# Bandit_the_Racoon.net
KiCad netlist of a schematic drawn in EAGLE
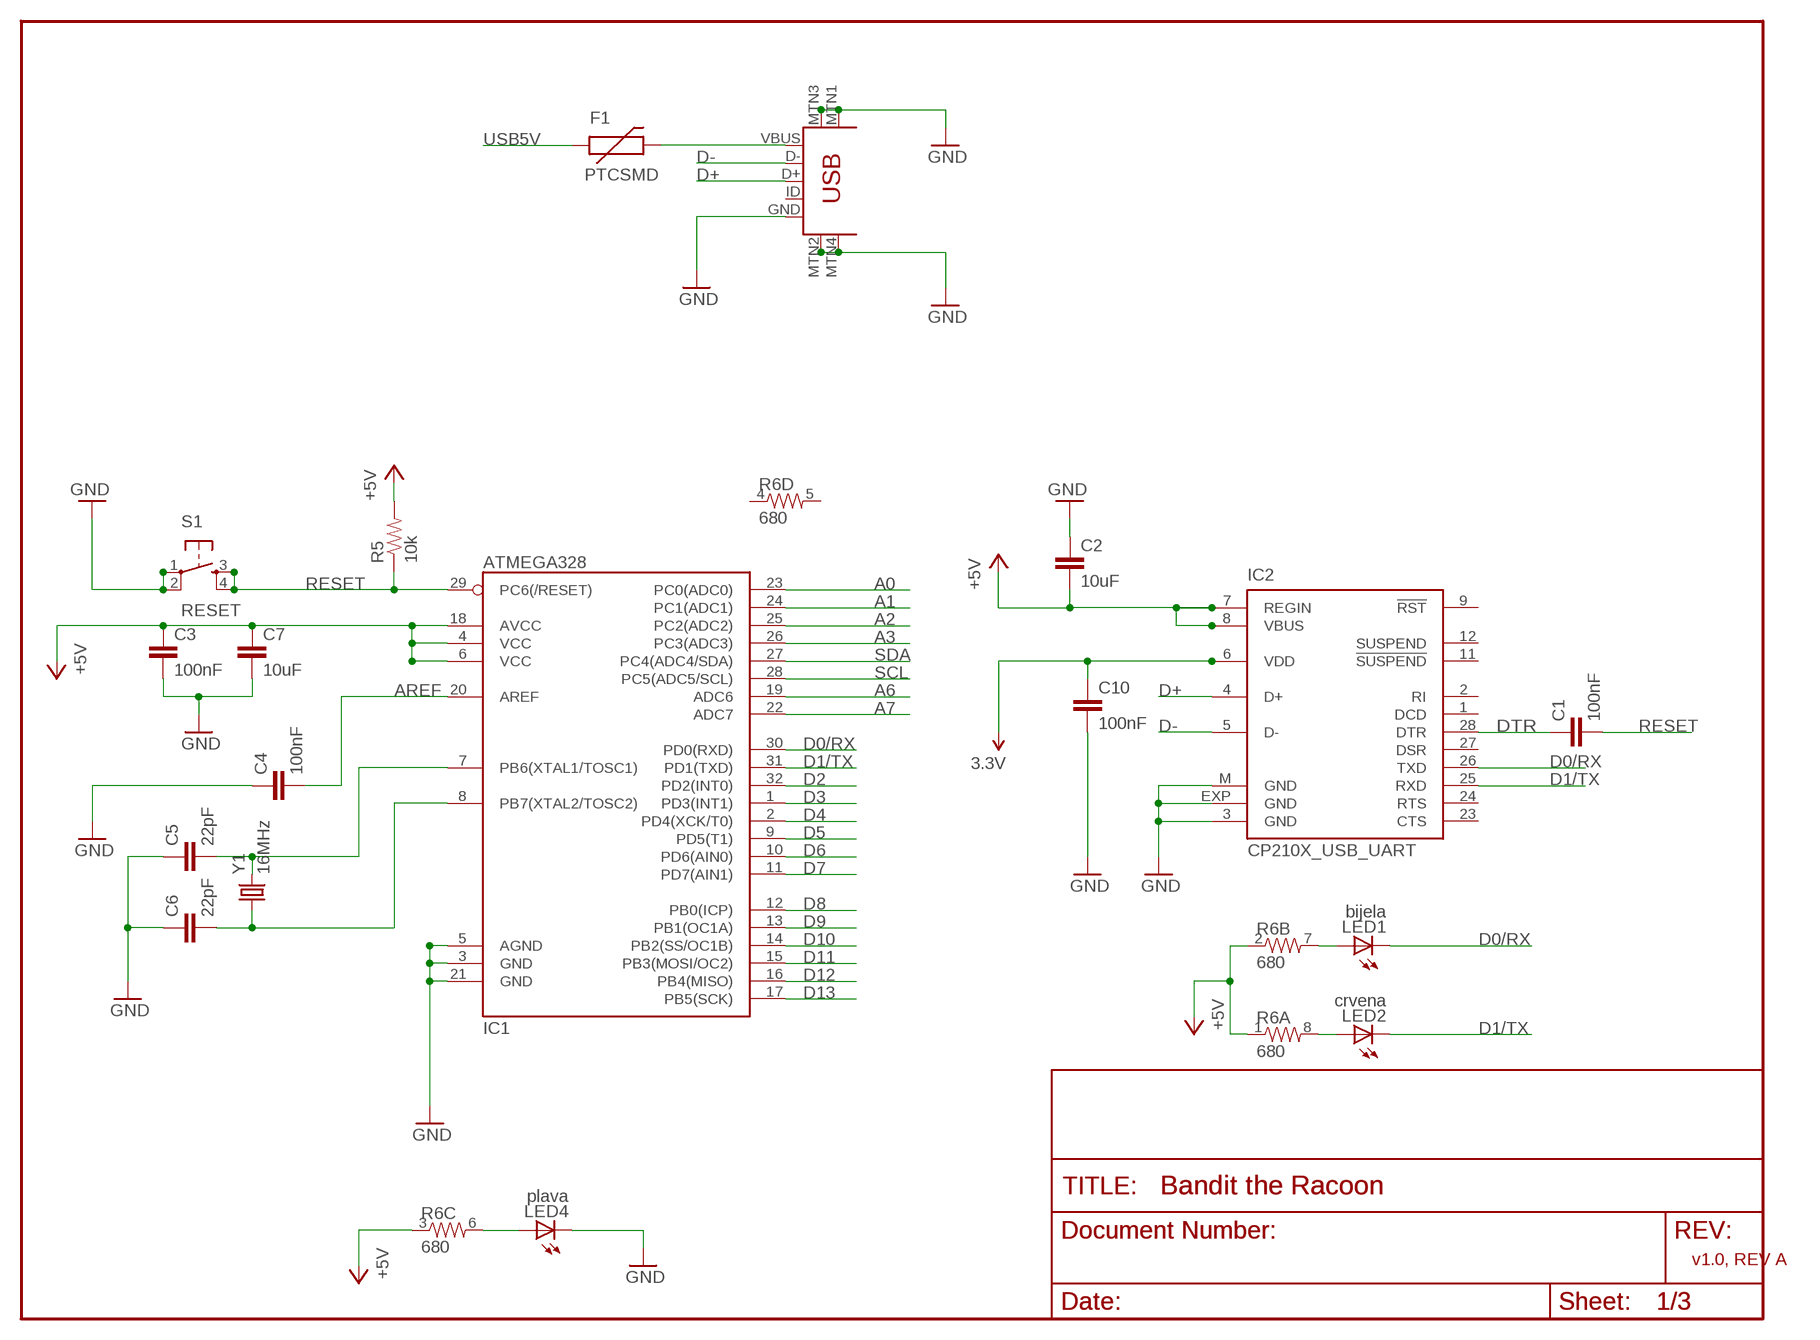
[diagram p0: schematic, sheet 1]
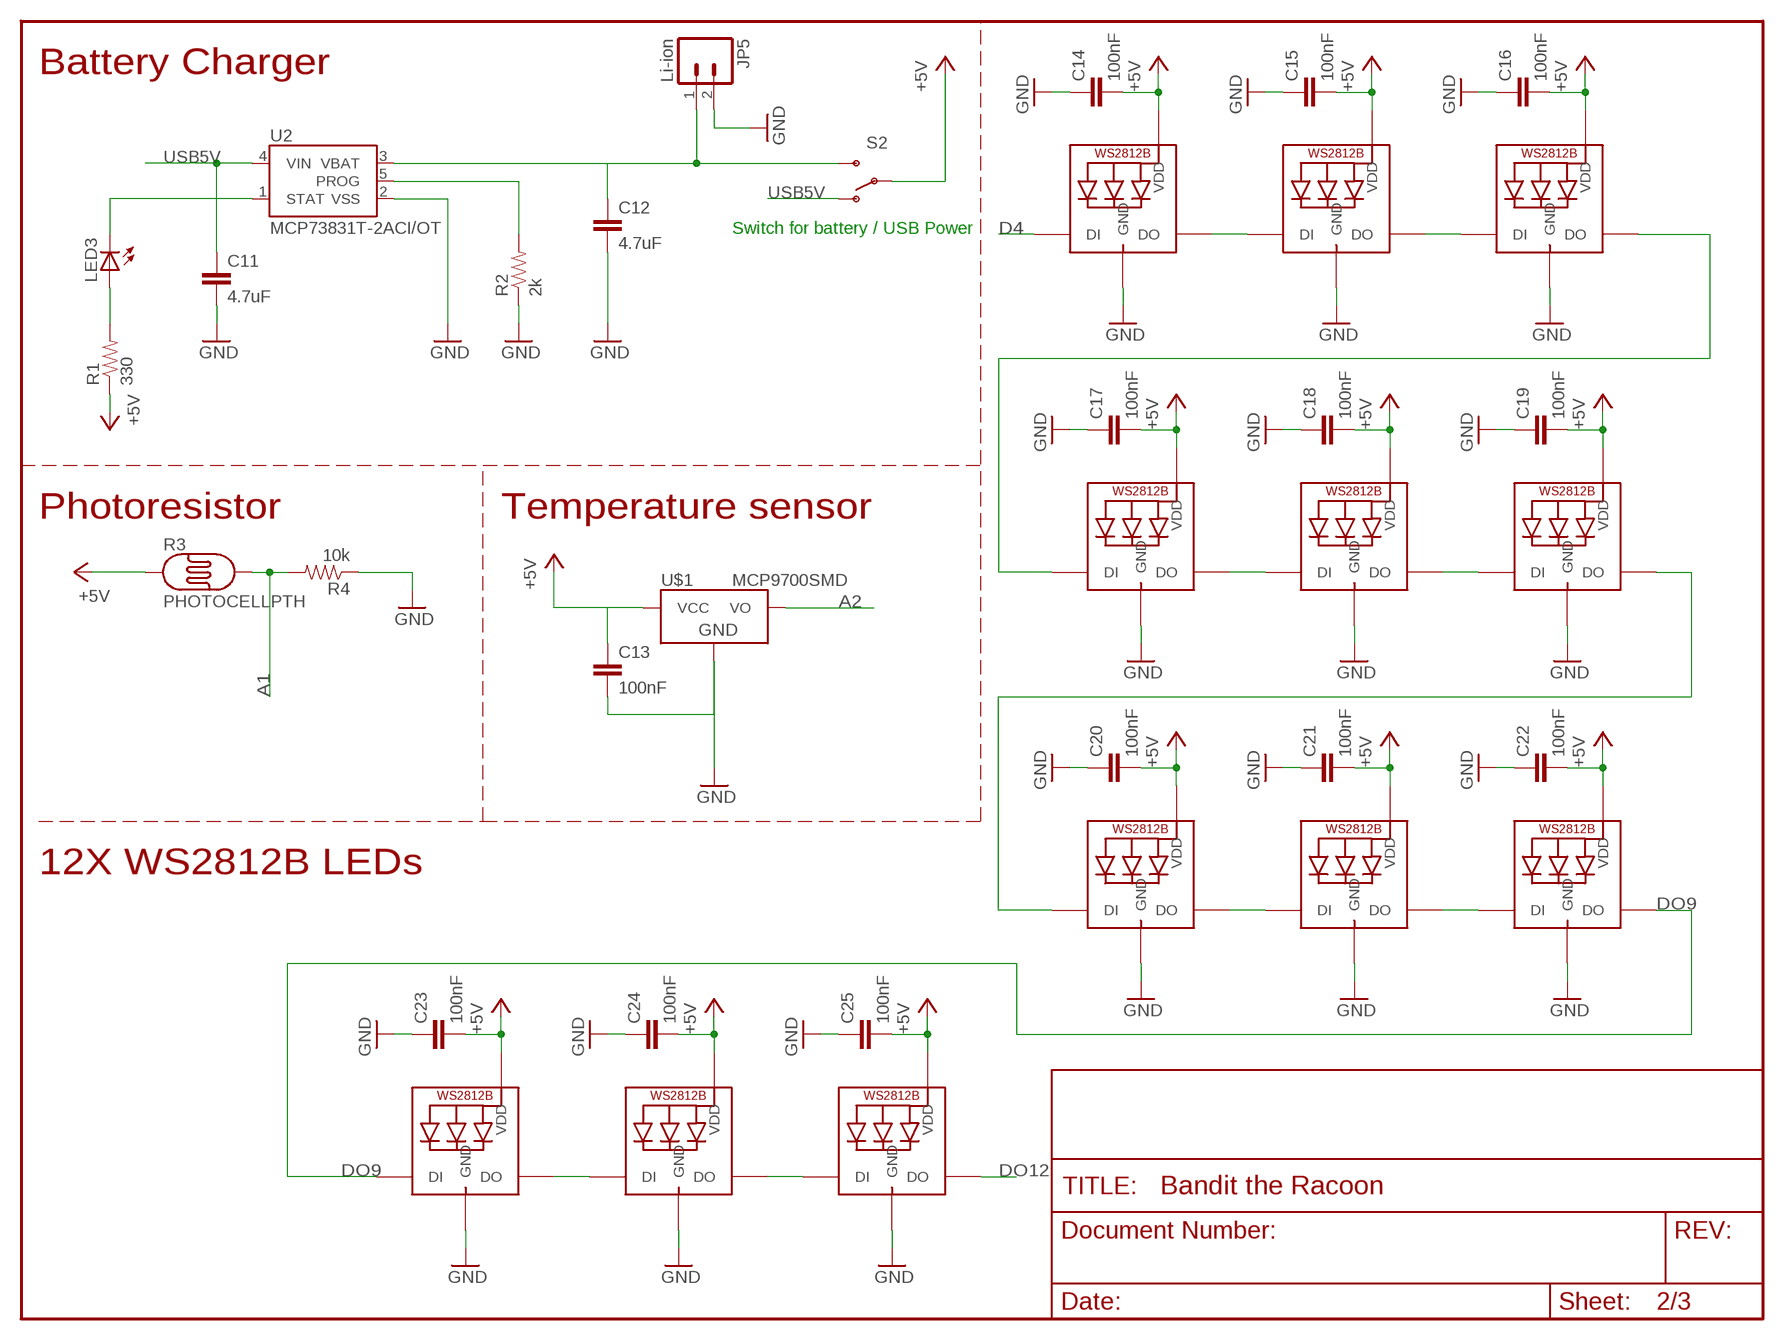
[diagram p1: schematic, sheet 2]
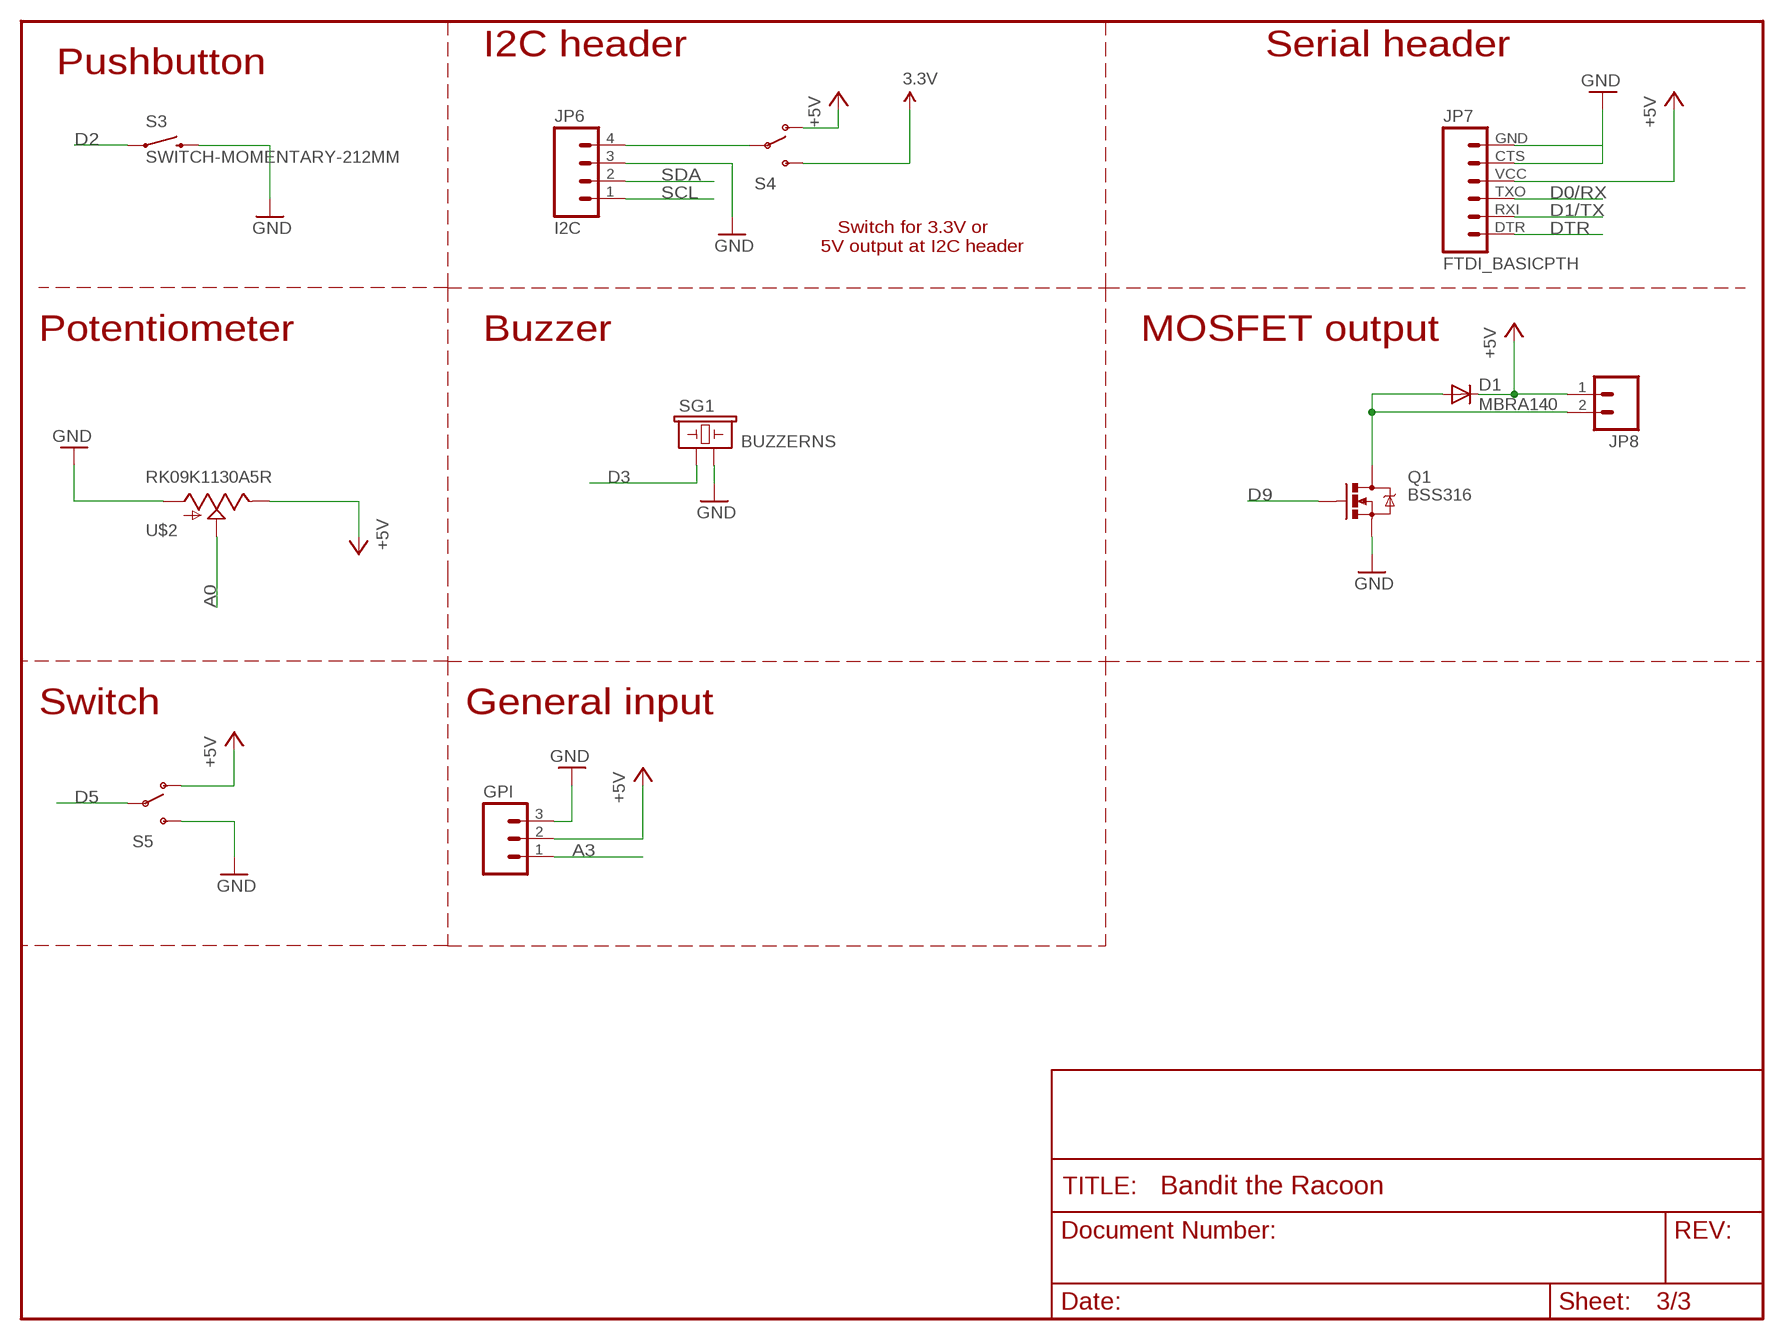
[diagram p2: schematic, sheet 3]

(export (version "E")
  (design (tool "Eeschema 10.0.6"))
  (components
    (comp (ref "C1")
      (value "100nF")
      (footprint "eagle-import:0603-CAP")
      (libsource (lib "eagle-import") (part "CAP0603-CAP"))
    )
    (comp (ref "C2")
      (value "10uF")
      (footprint "eagle-import:C3216")
      (libsource (lib "eagle-import") (part "C-EUC3216"))
    )
    (comp (ref "C3")
      (value "100nF")
      (footprint "eagle-import:0603-CAP")
      (libsource (lib "eagle-import") (part "CAP0603-CAP"))
    )
    (comp (ref "C4")
      (value "100nF")
      (footprint "eagle-import:0603-CAP")
      (libsource (lib "eagle-import") (part "CAP0603-CAP"))
    )
    (comp (ref "C5")
      (value "22pF")
      (footprint "eagle-import:0603-CAP")
      (libsource (lib "eagle-import") (part "CAP0603-CAP"))
    )
    (comp (ref "C6")
      (value "22pF")
      (footprint "eagle-import:0603-CAP")
      (libsource (lib "eagle-import") (part "CAP0603-CAP"))
    )
    (comp (ref "C7")
      (value "10uF")
      (footprint "eagle-import:C3216")
      (libsource (lib "eagle-import") (part "C-EUC3216"))
    )
    (comp (ref "C10")
      (value "100nF")
      (footprint "eagle-import:0603-CAP")
      (libsource (lib "eagle-import") (part "CAP0603-CAP"))
    )
    (comp (ref "F1")
      (value "PTCSMD")
      (footprint "eagle-import:PTC-1206")
      (libsource (lib "eagle-import") (part "PTCSMD"))
    )
    (comp (ref "IC1")
      (value "ATMEGA328")
      (footprint "eagle-import:TQFP32-08")
      (libsource (lib "eagle-import") (part "ATMEGA168"))
    )
    (comp (ref "IC2")
      (value "CP210X_USB_UART")
      (footprint "eagle-import:MLP28")
      (libsource (lib "eagle-import") (part "CP210X_USB_UART"))
    )
    (comp (ref "LED1")
      (value "bijela")
      (footprint "eagle-import:CHIP-LED0805")
      (libsource (lib "eagle-import") (part "LEDCHIP-LED0805"))
    )
    (comp (ref "LED2")
      (value "crvena")
      (footprint "eagle-import:CHIP-LED0805")
      (libsource (lib "eagle-import") (part "LEDCHIP-LED0805"))
    )
    (comp (ref "LED4")
      (value "plava")
      (footprint "eagle-import:CHIP-LED0805")
      (libsource (lib "eagle-import") (part "LEDCHIP-LED0805"))
    )
    (comp (ref "R5")
      (value "10k")
      (footprint "eagle-import:0603-RES")
      (libsource (lib "eagle-import") (part "RESISTOR0603-RES"))
    )
    (comp (ref "R6")
      (value "680")
      (footprint "eagle-import:0603-ARV")
      (libsource (lib "eagle-import") (part "RESISTOR-ARRAY0603-ARV"))
    )
    (comp (ref "S1")
      (value "RESET")
      (footprint "eagle-import:TACTILE_SWITCH_SMD")
      (libsource (lib "eagle-import") (part "TAC_SWITCHSMD"))
    )
    (comp (ref "U1")
      (value "USB-MINIB")
      (footprint "eagle-import:USB-MINIB")
      (libsource (lib "eagle-import") (part "USB-MINIB-5PIN"))
    )
    (comp (ref "Y1")
      (value "16MHz")
      (footprint "eagle-import:CRYSTAL-SMD-5X3")
      (libsource (lib "eagle-import") (part "CRYSTAL5X3"))
    )
    (comp (ref "C11")
      (value "4.7uF")
      (footprint "eagle-import:0805")
      (libsource (lib "eagle-import") (part "CAP0805"))
    )
    (comp (ref "C12")
      (value "4.7uF")
      (footprint "eagle-import:0805")
      (libsource (lib "eagle-import") (part "CAP0805"))
    )
    (comp (ref "C13")
      (value "100nF")
      (footprint "eagle-import:0603-CAP")
      (libsource (lib "eagle-import") (part "CAP0603-CAP"))
    )
    (comp (ref "C14")
      (value "100nF")
      (footprint "eagle-import:0603-CAP")
      (libsource (lib "eagle-import") (part "CAP0603-CAP"))
    )
    (comp (ref "C15")
      (value "100nF")
      (footprint "eagle-import:0603-CAP")
      (libsource (lib "eagle-import") (part "CAP0603-CAP"))
    )
    (comp (ref "C16")
      (value "100nF")
      (footprint "eagle-import:0603-CAP")
      (libsource (lib "eagle-import") (part "CAP0603-CAP"))
    )
    (comp (ref "C17")
      (value "100nF")
      (footprint "eagle-import:0603-CAP")
      (libsource (lib "eagle-import") (part "CAP0603-CAP"))
    )
    (comp (ref "C18")
      (value "100nF")
      (footprint "eagle-import:0603-CAP")
      (libsource (lib "eagle-import") (part "CAP0603-CAP"))
    )
    (comp (ref "C19")
      (value "100nF")
      (footprint "eagle-import:0603-CAP")
      (libsource (lib "eagle-import") (part "CAP0603-CAP"))
    )
    (comp (ref "C20")
      (value "100nF")
      (footprint "eagle-import:0603-CAP")
      (libsource (lib "eagle-import") (part "CAP0603-CAP"))
    )
    (comp (ref "C21")
      (value "100nF")
      (footprint "eagle-import:0603-CAP")
      (libsource (lib "eagle-import") (part "CAP0603-CAP"))
    )
    (comp (ref "C22")
      (value "100nF")
      (footprint "eagle-import:0603-CAP")
      (libsource (lib "eagle-import") (part "CAP0603-CAP"))
    )
    (comp (ref "C23")
      (value "100nF")
      (footprint "eagle-import:0603-CAP")
      (libsource (lib "eagle-import") (part "CAP0603-CAP"))
    )
    (comp (ref "C24")
      (value "100nF")
      (footprint "eagle-import:0603-CAP")
      (libsource (lib "eagle-import") (part "CAP0603-CAP"))
    )
    (comp (ref "C25")
      (value "100nF")
      (footprint "eagle-import:0603-CAP")
      (libsource (lib "eagle-import") (part "CAP0603-CAP"))
    )
    (comp (ref "JP5")
      (value "Li-ion")
      (footprint "eagle-import:JST-2-PTH")
      (libsource (lib "eagle-import") (part "M02JST-PTH-2"))
    )
    (comp (ref "LED3")
      (value "LEDCHIPLED_0805")
      (footprint "eagle-import:CHIPLED_0805")
      (libsource (lib "eagle-import") (part "LEDCHIPLED_0805"))
    )
    (comp (ref "LED5")
      (value "WS2812B5050")
      (footprint "eagle-import:WS2812B")
      (libsource (lib "eagle-import") (part "WS2812B5050"))
    )
    (comp (ref "LED6")
      (value "WS2812B5050")
      (footprint "eagle-import:WS2812B")
      (libsource (lib "eagle-import") (part "WS2812B5050"))
    )
    (comp (ref "LED7")
      (value "WS2812B5050")
      (footprint "eagle-import:WS2812B")
      (libsource (lib "eagle-import") (part "WS2812B5050"))
    )
    (comp (ref "LED8")
      (value "WS2812B5050")
      (footprint "eagle-import:WS2812B")
      (libsource (lib "eagle-import") (part "WS2812B5050"))
    )
    (comp (ref "LED9")
      (value "WS2812B5050")
      (footprint "eagle-import:WS2812B")
      (libsource (lib "eagle-import") (part "WS2812B5050"))
    )
    (comp (ref "LED10")
      (value "WS2812B5050")
      (footprint "eagle-import:WS2812B")
      (libsource (lib "eagle-import") (part "WS2812B5050"))
    )
    (comp (ref "LED11")
      (value "WS2812B5050")
      (footprint "eagle-import:WS2812B")
      (libsource (lib "eagle-import") (part "WS2812B5050"))
    )
    (comp (ref "LED12")
      (value "WS2812B5050")
      (footprint "eagle-import:WS2812B")
      (libsource (lib "eagle-import") (part "WS2812B5050"))
    )
    (comp (ref "LED13")
      (value "WS2812B5050")
      (footprint "eagle-import:WS2812B")
      (libsource (lib "eagle-import") (part "WS2812B5050"))
    )
    (comp (ref "LED14")
      (value "WS2812B5050")
      (footprint "eagle-import:WS2812B")
      (libsource (lib "eagle-import") (part "WS2812B5050"))
    )
    (comp (ref "LED15")
      (value "WS2812B5050")
      (footprint "eagle-import:WS2812B")
      (libsource (lib "eagle-import") (part "WS2812B5050"))
    )
    (comp (ref "LED16")
      (value "WS2812B5050")
      (footprint "eagle-import:WS2812B")
      (libsource (lib "eagle-import") (part "WS2812B5050"))
    )
    (comp (ref "R1")
      (value "330")
      (footprint "eagle-import:0603-RES")
      (libsource (lib "eagle-import") (part "RESISTOR0603-RES"))
    )
    (comp (ref "R2")
      (value "2k")
      (footprint "eagle-import:0603-RES")
      (libsource (lib "eagle-import") (part "RESISTOR0603-RES"))
    )
    (comp (ref "R3")
      (value "PHOTOCELLPTH")
      (footprint "eagle-import:PHOTOCELL")
      (libsource (lib "eagle-import") (part "PHOTOCELLPTH"))
    )
    (comp (ref "R4")
      (value "10k")
      (footprint "eagle-import:0603-RES")
      (libsource (lib "eagle-import") (part "RESISTOR0603-RES"))
    )
    (comp (ref "S2")
      (value "SWITCH-SPST-SMD-A")
      (footprint "eagle-import:SWITCH-SPST-SMD-A")
      (libsource (lib "eagle-import") (part "SWITCH-SPST-SMD-A"))
    )
    (comp (ref "U$1")
      (value "MCP9700SMD")
      (footprint "eagle-import:SOT23-3")
      (libsource (lib "eagle-import") (part "MCP9700SMD"))
    )
    (comp (ref "U2")
      (value "MCP73831T-2ACI/OT")
      (footprint "eagle-import:SOT23-5")
      (libsource (lib "eagle-import") (part "MCP73831"))
    )
    (comp (ref "D1")
      (value "MBRA140")
      (footprint "eagle-import:SMA-DIODE")
      (libsource (lib "eagle-import") (part "DIODESMA"))
    )
    (comp (ref "GPI")
      (value "M03LONGPADS")
      (footprint "eagle-import:1X03_LONGPADS")
      (libsource (lib "eagle-import") (part "M03LONGPADS"))
    )
    (comp (ref "JP6")
      (value "I2C")
      (footprint "eagle-import:1X04_LONGPADS")
      (libsource (lib "eagle-import") (part "M04LONGPADS"))
    )
    (comp (ref "JP7")
      (value "FTDI_BASICPTH")
      (footprint "eagle-import:FTDI_BASIC")
      (libsource (lib "eagle-import") (part "FTDI_BASICPTH"))
    )
    (comp (ref "JP8")
      (value "M02PTH")
      (footprint "eagle-import:1X02")
      (libsource (lib "eagle-import") (part "M02PTH"))
    )
    (comp (ref "Q1")
      (value "BSS316")
      (footprint "eagle-import:SOT23-3")
      (libsource (lib "eagle-import") (part "MOSFET-NCHANNELSMD"))
    )
    (comp (ref "S3")
      (value "SWITCH-MOMENTARY-212MM")
      (footprint "eagle-import:TACTILE-PTH-12MM")
      (libsource (lib "eagle-import") (part "SWITCH-MOMENTARY-212MM"))
    )
    (comp (ref "S4")
      (value "SWITCH-SPST-SMD-A")
      (footprint "eagle-import:SWITCH-SPST-SMD-A")
      (libsource (lib "eagle-import") (part "SWITCH-SPST-SMD-A"))
    )
    (comp (ref "S5")
      (value "SWITCH-SPSTKIT")
      (footprint "eagle-import:SWITCH-SPDT_KIT")
      (libsource (lib "eagle-import") (part "SWITCH-SPSTKIT"))
    )
    (comp (ref "SG1")
      (value "BUZZERNS")
      (footprint "eagle-import:BUZZER-12MM-NS")
      (libsource (lib "eagle-import") (part "BUZZERNS"))
    )
    (comp (ref "U$2")
      (value "RK09K1130A5R")
      (footprint "eagle-import:ALPS_POT")
      (libsource (lib "eagle-import") (part "POT"))
    )
  )
  (nets
    (net (code "1") (name "+5V") (class "Default")
      (node (ref "C13") (pin "1") (pinfunction "1_1") (pintype "passive"))
      (node (ref "C14") (pin "2") (pinfunction "2_2") (pintype "passive"))
      (node (ref "C15") (pin "2") (pinfunction "2_2") (pintype "passive"))
      (node (ref "C16") (pin "2") (pinfunction "2_2") (pintype "passive"))
      (node (ref "C17") (pin "2") (pinfunction "2_2") (pintype "passive"))
      (node (ref "C18") (pin "2") (pinfunction "2_2") (pintype "passive"))
      (node (ref "C19") (pin "2") (pinfunction "2_2") (pintype "passive"))
      (node (ref "C2") (pin "2") (pinfunction "2_2") (pintype "passive"))
      (node (ref "C20") (pin "2") (pinfunction "2_2") (pintype "passive"))
      (node (ref "C21") (pin "2") (pinfunction "2_2") (pintype "passive"))
      (node (ref "C22") (pin "2") (pinfunction "2_2") (pintype "passive"))
      (node (ref "C23") (pin "2") (pinfunction "2_2") (pintype "passive"))
      (node (ref "C24") (pin "2") (pinfunction "2_2") (pintype "passive"))
      (node (ref "C25") (pin "2") (pinfunction "2_2") (pintype "passive"))
      (node (ref "C3") (pin "1") (pinfunction "1_1") (pintype "passive"))
      (node (ref "C7") (pin "1") (pinfunction "1_1") (pintype "passive"))
      (node (ref "D1") (pin "C") (pinfunction "C_C") (pintype "passive"))
      (node (ref "GPI") (pin "2") (pinfunction "2_2") (pintype "passive"))
      (node (ref "IC1") (pin "18") (pinfunction "AVCC_18") (pintype "bidirectional"))
      (node (ref "IC1") (pin "4") (pinfunction "VCC_4") (pintype "bidirectional"))
      (node (ref "IC1") (pin "6") (pinfunction "VCC_6") (pintype "bidirectional"))
      (node (ref "IC2") (pin "7") (pinfunction "REGIN_7") (pintype "passive"))
      (node (ref "IC2") (pin "8") (pinfunction "VBUS_8") (pintype "input"))
      (node (ref "JP7") (pin "VCC") (pinfunction "4_VCC") (pintype "passive"))
      (node (ref "JP8") (pin "1") (pinfunction "1_1") (pintype "passive"))
      (node (ref "LED10") (pin "1-VDD") (pinfunction "VDD_1-VDD") (pintype "power_in"))
      (node (ref "LED11") (pin "1-VDD") (pinfunction "VDD_1-VDD") (pintype "power_in"))
      (node (ref "LED12") (pin "1-VDD") (pinfunction "VDD_1-VDD") (pintype "power_in"))
      (node (ref "LED13") (pin "1-VDD") (pinfunction "VDD_1-VDD") (pintype "power_in"))
      (node (ref "LED14") (pin "1-VDD") (pinfunction "VDD_1-VDD") (pintype "power_in"))
      (node (ref "LED15") (pin "1-VDD") (pinfunction "VDD_1-VDD") (pintype "power_in"))
      (node (ref "LED16") (pin "1-VDD") (pinfunction "VDD_1-VDD") (pintype "power_in"))
      (node (ref "LED5") (pin "1-VDD") (pinfunction "VDD_1-VDD") (pintype "power_in"))
      (node (ref "LED6") (pin "1-VDD") (pinfunction "VDD_1-VDD") (pintype "power_in"))
      (node (ref "LED7") (pin "1-VDD") (pinfunction "VDD_1-VDD") (pintype "power_in"))
      (node (ref "LED8") (pin "1-VDD") (pinfunction "VDD_1-VDD") (pintype "power_in"))
      (node (ref "LED9") (pin "1-VDD") (pinfunction "VDD_1-VDD") (pintype "power_in"))
      (node (ref "R1") (pin "1") (pinfunction "1_1") (pintype "passive"))
      (node (ref "R3") (pin "1") (pinfunction "P$1_1") (pintype "bidirectional"))
      (node (ref "R5") (pin "2") (pinfunction "2_2") (pintype "passive"))
      (node (ref "R6") (pin "1") (pinfunction "1_1") (pintype "passive"))
      (node (ref "R6") (pin "2") (pinfunction "1_2") (pintype "passive"))
      (node (ref "R6") (pin "3") (pinfunction "1_3") (pintype "passive"))
      (node (ref "S2") (pin "2") (pinfunction "P_2") (pintype "passive"))
      (node (ref "S4") (pin "1") (pinfunction "O_1") (pintype "passive"))
      (node (ref "S5") (pin "1") (pinfunction "O_1") (pintype "passive"))
      (node (ref "U$1") (pin "1") (pinfunction "VCC_1") (pintype "bidirectional"))
      (node (ref "U$2") (pin "P$1") (pinfunction "E_P$1") (pintype "passive"))
    )
    (net (code "2") (name "3.3V") (class "Default")
      (node (ref "C10") (pin "1") (pinfunction "1_1") (pintype "passive"))
      (node (ref "IC2") (pin "6") (pinfunction "VDD_6") (pintype "power_in"))
      (node (ref "S4") (pin "3") (pinfunction "S_3") (pintype "passive"))
    )
    (net (code "3") (name "A0") (class "Default")
      (node (ref "IC1") (pin "23") (pinfunction "PC0(ADC0)_23") (pintype "bidirectional"))
      (node (ref "U$2") (pin "P$2") (pinfunction "S_P$2") (pintype "passive"))
    )
    (net (code "4") (name "A1") (class "Default")
      (node (ref "IC1") (pin "24") (pinfunction "PC1(ADC1)_24") (pintype "bidirectional"))
      (node (ref "R3") (pin "2") (pinfunction "P$2_2") (pintype "bidirectional"))
      (node (ref "R4") (pin "2") (pinfunction "2_2") (pintype "passive"))
    )
    (net (code "5") (name "A2") (class "Default")
      (node (ref "IC1") (pin "25") (pinfunction "PC2(ADC2)_25") (pintype "bidirectional"))
      (node (ref "U$1") (pin "2") (pinfunction "VO_2") (pintype "bidirectional"))
    )
    (net (code "6") (name "A3") (class "Default")
      (node (ref "GPI") (pin "1") (pinfunction "1_1") (pintype "passive"))
      (node (ref "IC1") (pin "26") (pinfunction "PC3(ADC3)_26") (pintype "bidirectional"))
    )
    (net (code "7") (name "A6") (class "Default")
      (node (ref "IC1") (pin "19") (pinfunction "ADC6_19") (pintype "bidirectional"))
    )
    (net (code "8") (name "A7") (class "Default")
      (node (ref "IC1") (pin "22") (pinfunction "ADC7_22") (pintype "bidirectional"))
    )
    (net (code "9") (name "AREF") (class "Default")
      (node (ref "C4") (pin "2") (pinfunction "2_2") (pintype "passive"))
      (node (ref "IC1") (pin "20") (pinfunction "AREF_20") (pintype "bidirectional"))
    )
    (net (code "10") (name "D+") (class "Default")
      (node (ref "IC2") (pin "4") (pinfunction "D+_4") (pintype "bidirectional"))
      (node (ref "U1") (pin "D+") (pinfunction "D+_D+") (pintype "bidirectional"))
    )
    (net (code "11") (name "D-") (class "Default")
      (node (ref "IC2") (pin "5") (pinfunction "D-_5") (pintype "bidirectional"))
      (node (ref "U1") (pin "D-") (pinfunction "D-_D-") (pintype "bidirectional"))
    )
    (net (code "12") (name "D0{slash}RX") (class "Default")
      (node (ref "IC1") (pin "30") (pinfunction "PD0(RXD)_30") (pintype "bidirectional"))
      (node (ref "IC2") (pin "26") (pinfunction "TXD_26") (pintype "output"))
      (node (ref "JP7") (pin "TXO") (pinfunction "3_TXO") (pintype "passive"))
      (node (ref "LED1") (pin "C") (pinfunction "C_C") (pintype "passive"))
    )
    (net (code "13") (name "D1{slash}TX") (class "Default")
      (node (ref "IC1") (pin "31") (pinfunction "PD1(TXD)_31") (pintype "bidirectional"))
      (node (ref "IC2") (pin "25") (pinfunction "RXD_25") (pintype "input"))
      (node (ref "JP7") (pin "RXI") (pinfunction "2_RXI") (pintype "passive"))
      (node (ref "LED2") (pin "C") (pinfunction "C_C") (pintype "passive"))
    )
    (net (code "14") (name "D2") (class "Default")
      (node (ref "IC1") (pin "32") (pinfunction "PD2(INT0)_32") (pintype "bidirectional"))
      (node (ref "S3") (pin "1") (pinfunction "1_1") (pintype "passive"))
    )
    (net (code "15") (name "D3") (class "Default")
      (node (ref "IC1") (pin "1") (pinfunction "PD3(INT1)_1") (pintype "bidirectional"))
      (node (ref "SG1") (pin "+") (pinfunction "1_+") (pintype "passive"))
    )
    (net (code "16") (name "D4") (class "Default")
      (node (ref "IC1") (pin "2") (pinfunction "PD4(XCK/T0)_2") (pintype "bidirectional"))
      (node (ref "LED5") (pin "4-DIN") (pinfunction "DI_4-DIN") (pintype "input"))
    )
    (net (code "17") (name "D5") (class "Default")
      (node (ref "IC1") (pin "9") (pinfunction "PD5(T1)_9") (pintype "bidirectional"))
      (node (ref "S5") (pin "2") (pinfunction "P_2") (pintype "passive"))
    )
    (net (code "18") (name "D6") (class "Default")
      (node (ref "IC1") (pin "10") (pinfunction "PD6(AIN0)_10") (pintype "bidirectional"))
    )
    (net (code "19") (name "D7") (class "Default")
      (node (ref "IC1") (pin "11") (pinfunction "PD7(AIN1)_11") (pintype "bidirectional"))
    )
    (net (code "20") (name "D8") (class "Default")
      (node (ref "IC1") (pin "12") (pinfunction "PB0(ICP)_12") (pintype "bidirectional"))
    )
    (net (code "21") (name "D9") (class "Default")
      (node (ref "IC1") (pin "13") (pinfunction "PB1(OC1A)_13") (pintype "bidirectional"))
      (node (ref "Q1") (pin "1") (pinfunction "G_1") (pintype "passive"))
    )
    (net (code "22") (name "D10") (class "Default")
      (node (ref "IC1") (pin "14") (pinfunction "PB2(SS/OC1B)_14") (pintype "bidirectional"))
    )
    (net (code "23") (name "D11") (class "Default")
      (node (ref "IC1") (pin "15") (pinfunction "PB3(MOSI/OC2)_15") (pintype "bidirectional"))
    )
    (net (code "24") (name "D12") (class "Default")
      (node (ref "IC1") (pin "16") (pinfunction "PB4(MISO)_16") (pintype "bidirectional"))
    )
    (net (code "25") (name "D13") (class "Default")
      (node (ref "IC1") (pin "17") (pinfunction "PB5(SCK)_17") (pintype "bidirectional"))
    )
    (net (code "26") (name "DO9") (class "Default")
      (node (ref "LED13") (pin "2-DOUT") (pinfunction "DO_2-DOUT") (pintype "output"))
      (node (ref "LED14") (pin "4-DIN") (pinfunction "DI_4-DIN") (pintype "input"))
    )
    (net (code "27") (name "DO12") (class "Default")
      (node (ref "LED16") (pin "2-DOUT") (pinfunction "DO_2-DOUT") (pintype "output"))
    )
    (net (code "28") (name "DTR") (class "Default")
      (node (ref "C1") (pin "1") (pinfunction "1_1") (pintype "passive"))
      (node (ref "IC2") (pin "28") (pinfunction "DTR_28") (pintype "output"))
      (node (ref "JP7") (pin "DTR") (pinfunction "1_DTR") (pintype "passive"))
    )
    (net (code "29") (name "GND") (class "Default")
      (node (ref "C10") (pin "2") (pinfunction "2_2") (pintype "passive"))
      (node (ref "C11") (pin "2") (pinfunction "2_2") (pintype "passive"))
      (node (ref "C12") (pin "2") (pinfunction "2_2") (pintype "passive"))
      (node (ref "C13") (pin "2") (pinfunction "2_2") (pintype "passive"))
      (node (ref "C14") (pin "1") (pinfunction "1_1") (pintype "passive"))
      (node (ref "C15") (pin "1") (pinfunction "1_1") (pintype "passive"))
      (node (ref "C16") (pin "1") (pinfunction "1_1") (pintype "passive"))
      (node (ref "C17") (pin "1") (pinfunction "1_1") (pintype "passive"))
      (node (ref "C18") (pin "1") (pinfunction "1_1") (pintype "passive"))
      (node (ref "C19") (pin "1") (pinfunction "1_1") (pintype "passive"))
      (node (ref "C2") (pin "1") (pinfunction "1_1") (pintype "passive"))
      (node (ref "C20") (pin "1") (pinfunction "1_1") (pintype "passive"))
      (node (ref "C21") (pin "1") (pinfunction "1_1") (pintype "passive"))
      (node (ref "C22") (pin "1") (pinfunction "1_1") (pintype "passive"))
      (node (ref "C23") (pin "1") (pinfunction "1_1") (pintype "passive"))
      (node (ref "C24") (pin "1") (pinfunction "1_1") (pintype "passive"))
      (node (ref "C25") (pin "1") (pinfunction "1_1") (pintype "passive"))
      (node (ref "C3") (pin "2") (pinfunction "2_2") (pintype "passive"))
      (node (ref "C4") (pin "1") (pinfunction "1_1") (pintype "passive"))
      (node (ref "C5") (pin "1") (pinfunction "1_1") (pintype "passive"))
      (node (ref "C6") (pin "1") (pinfunction "1_1") (pintype "passive"))
      (node (ref "C7") (pin "2") (pinfunction "2_2") (pintype "passive"))
      (node (ref "GPI") (pin "3") (pinfunction "3_3") (pintype "passive"))
      (node (ref "IC1") (pin "21") (pinfunction "GND_21") (pintype "bidirectional"))
      (node (ref "IC1") (pin "3") (pinfunction "GND_3") (pintype "bidirectional"))
      (node (ref "IC1") (pin "5") (pinfunction "AGND_5") (pintype "bidirectional"))
      (node (ref "IC2") (pin "3") (pinfunction "GND_3") (pintype "power_in"))
      (node (ref "IC2") (pin "EXP") (pinfunction "GND_EXP") (pintype "power_in"))
      (node (ref "IC2") (pin "M") (pinfunction "GND_M") (pintype "power_in"))
      (node (ref "JP5") (pin "2") (pinfunction "2_2") (pintype "passive"))
      (node (ref "JP6") (pin "3") (pinfunction "3_3") (pintype "passive"))
      (node (ref "JP7") (pin "CTS") (pinfunction "5_CTS") (pintype "passive"))
      (node (ref "JP7") (pin "GND") (pinfunction "6_GND") (pintype "passive"))
      (node (ref "LED10") (pin "3-GND") (pinfunction "GND_3-GND") (pintype "power_in"))
      (node (ref "LED11") (pin "3-GND") (pinfunction "GND_3-GND") (pintype "power_in"))
      (node (ref "LED12") (pin "3-GND") (pinfunction "GND_3-GND") (pintype "power_in"))
      (node (ref "LED13") (pin "3-GND") (pinfunction "GND_3-GND") (pintype "power_in"))
      (node (ref "LED14") (pin "3-GND") (pinfunction "GND_3-GND") (pintype "power_in"))
      (node (ref "LED15") (pin "3-GND") (pinfunction "GND_3-GND") (pintype "power_in"))
      (node (ref "LED16") (pin "3-GND") (pinfunction "GND_3-GND") (pintype "power_in"))
      (node (ref "LED4") (pin "C") (pinfunction "C_C") (pintype "passive"))
      (node (ref "LED5") (pin "3-GND") (pinfunction "GND_3-GND") (pintype "power_in"))
      (node (ref "LED6") (pin "3-GND") (pinfunction "GND_3-GND") (pintype "power_in"))
      (node (ref "LED7") (pin "3-GND") (pinfunction "GND_3-GND") (pintype "power_in"))
      (node (ref "LED8") (pin "3-GND") (pinfunction "GND_3-GND") (pintype "power_in"))
      (node (ref "LED9") (pin "3-GND") (pinfunction "GND_3-GND") (pintype "power_in"))
      (node (ref "Q1") (pin "2") (pinfunction "S_2") (pintype "passive"))
      (node (ref "R2") (pin "1") (pinfunction "1_1") (pintype "passive"))
      (node (ref "R4") (pin "1") (pinfunction "1_1") (pintype "passive"))
      (node (ref "S1") (pin "1") (pinfunction "1_1") (pintype "passive"))
      (node (ref "S1") (pin "2") (pinfunction "2_2") (pintype "passive"))
      (node (ref "S3") (pin "3") (pinfunction "2_3") (pintype "passive"))
      (node (ref "S5") (pin "3") (pinfunction "S_3") (pintype "passive"))
      (node (ref "SG1") (pin "-") (pinfunction "2_-") (pintype "passive"))
      (node (ref "U$1") (pin "3") (pinfunction "GND_3") (pintype "bidirectional"))
      (node (ref "U$2") (pin "P$3") (pinfunction "A_P$3") (pintype "passive"))
      (node (ref "U1") (pin "GND") (pinfunction "GND_GND") (pintype "bidirectional"))
      (node (ref "U1") (pin "MTN1") (pinfunction "MTN2_MTN1") (pintype "bidirectional"))
      (node (ref "U1") (pin "MTN2") (pinfunction "MTN3_MTN2") (pintype "bidirectional"))
      (node (ref "U1") (pin "MTN3") (pinfunction "MTN1_MTN3") (pintype "bidirectional"))
      (node (ref "U1") (pin "MTN4") (pinfunction "MTN4_MTN4") (pintype "bidirectional"))
      (node (ref "U2") (pin "2") (pinfunction "VSS_2") (pintype "power_in"))
    )
    (net (code "30") (name "Net-(F1-Pad2)") (class "Default")
      (node (ref "F1") (pin "2") (pinfunction "2_2") (pintype "bidirectional"))
      (node (ref "U1") (pin "VBUS") (pinfunction "VBUS_VBUS") (pintype "bidirectional"))
    )
    (net (code "31") (name "Net-(IC1-PB6(XTAL1{slash}TOSC1))") (class "Default")
      (node (ref "C5") (pin "2") (pinfunction "2_2") (pintype "passive"))
      (node (ref "IC1") (pin "7") (pinfunction "PB6(XTAL1/TOSC1)_7") (pintype "bidirectional"))
      (node (ref "Y1") (pin "3") (pinfunction "2_3") (pintype "passive"))
    )
    (net (code "32") (name "Net-(IC1-PB7(XTAL2{slash}TOSC2))") (class "Default")
      (node (ref "C6") (pin "2") (pinfunction "2_2") (pintype "passive"))
      (node (ref "IC1") (pin "8") (pinfunction "PB7(XTAL2/TOSC2)_8") (pintype "bidirectional"))
      (node (ref "Y1") (pin "1") (pinfunction "1_1") (pintype "passive"))
    )
    (net (code "33") (name "Net-(LED3-PadA)") (class "Default")
      (node (ref "LED3") (pin "A") (pinfunction "A_A") (pintype "passive"))
      (node (ref "R1") (pin "2") (pinfunction "2_2") (pintype "passive"))
    )
    (net (code "34") (name "Net-(LED5-DO)") (class "Default")
      (node (ref "LED5") (pin "2-DOUT") (pinfunction "DO_2-DOUT") (pintype "output"))
      (node (ref "LED6") (pin "4-DIN") (pinfunction "DI_4-DIN") (pintype "input"))
    )
    (net (code "35") (name "Net-(LED6-DO)") (class "Default")
      (node (ref "LED6") (pin "2-DOUT") (pinfunction "DO_2-DOUT") (pintype "output"))
      (node (ref "LED7") (pin "4-DIN") (pinfunction "DI_4-DIN") (pintype "input"))
    )
    (net (code "36") (name "Net-(LED7-DO)") (class "Default")
      (node (ref "LED7") (pin "2-DOUT") (pinfunction "DO_2-DOUT") (pintype "output"))
      (node (ref "LED8") (pin "4-DIN") (pinfunction "DI_4-DIN") (pintype "input"))
    )
    (net (code "37") (name "Net-(LED8-DO)") (class "Default")
      (node (ref "LED8") (pin "2-DOUT") (pinfunction "DO_2-DOUT") (pintype "output"))
      (node (ref "LED9") (pin "4-DIN") (pinfunction "DI_4-DIN") (pintype "input"))
    )
    (net (code "38") (name "Net-(LED10-DI)") (class "Default")
      (node (ref "LED10") (pin "4-DIN") (pinfunction "DI_4-DIN") (pintype "input"))
      (node (ref "LED9") (pin "2-DOUT") (pinfunction "DO_2-DOUT") (pintype "output"))
    )
    (net (code "39") (name "Net-(LED10-DO)") (class "Default")
      (node (ref "LED10") (pin "2-DOUT") (pinfunction "DO_2-DOUT") (pintype "output"))
      (node (ref "LED11") (pin "4-DIN") (pinfunction "DI_4-DIN") (pintype "input"))
    )
    (net (code "40") (name "Net-(LED11-DO)") (class "Default")
      (node (ref "LED11") (pin "2-DOUT") (pinfunction "DO_2-DOUT") (pintype "output"))
      (node (ref "LED12") (pin "4-DIN") (pinfunction "DI_4-DIN") (pintype "input"))
    )
    (net (code "41") (name "Net-(LED12-DO)") (class "Default")
      (node (ref "LED12") (pin "2-DOUT") (pinfunction "DO_2-DOUT") (pintype "output"))
      (node (ref "LED13") (pin "4-DIN") (pinfunction "DI_4-DIN") (pintype "input"))
    )
    (net (code "42") (name "Net-(LED14-DO)") (class "Default")
      (node (ref "LED14") (pin "2-DOUT") (pinfunction "DO_2-DOUT") (pintype "output"))
      (node (ref "LED15") (pin "4-DIN") (pinfunction "DI_4-DIN") (pintype "input"))
    )
    (net (code "43") (name "Net-(LED15-DO)") (class "Default")
      (node (ref "LED15") (pin "2-DOUT") (pinfunction "DO_2-DOUT") (pintype "output"))
      (node (ref "LED16") (pin "4-DIN") (pinfunction "DI_4-DIN") (pintype "input"))
    )
    (net (code "44") (name "Net-(Q1-D)") (class "Default")
      (node (ref "D1") (pin "A") (pinfunction "A_A") (pintype "passive"))
      (node (ref "JP8") (pin "2") (pinfunction "2_2") (pintype "passive"))
      (node (ref "Q1") (pin "3") (pinfunction "D_3") (pintype "passive"))
    )
    (net (code "45") (name "Net-(R6A-2)") (class "Default")
      (node (ref "LED2") (pin "A") (pinfunction "A_A") (pintype "passive"))
      (node (ref "R6") (pin "8") (pinfunction "2_8") (pintype "passive"))
    )
    (net (code "46") (name "Net-(R6B-2)") (class "Default")
      (node (ref "LED1") (pin "A") (pinfunction "A_A") (pintype "passive"))
      (node (ref "R6") (pin "7") (pinfunction "2_7") (pintype "passive"))
    )
    (net (code "47") (name "Net-(R6C-2)") (class "Default")
      (node (ref "LED4") (pin "A") (pinfunction "A_A") (pintype "passive"))
      (node (ref "R6") (pin "6") (pinfunction "2_6") (pintype "passive"))
    )
    (net (code "48") (name "Net-(S2-S)") (class "Default")
      (node (ref "C12") (pin "1") (pinfunction "1_1") (pintype "passive"))
      (node (ref "JP5") (pin "1") (pinfunction "1_1") (pintype "passive"))
      (node (ref "S2") (pin "3") (pinfunction "S_3") (pintype "passive"))
      (node (ref "U2") (pin "3") (pinfunction "VBAT_3") (pintype "power_in"))
    )
    (net (code "49") (name "Net-(S4-P)") (class "Default")
      (node (ref "JP6") (pin "4") (pinfunction "4_4") (pintype "passive"))
      (node (ref "S4") (pin "2") (pinfunction "P_2") (pintype "passive"))
    )
    (net (code "50") (name "Net-(U2-PROG)") (class "Default")
      (node (ref "R2") (pin "2") (pinfunction "2_2") (pintype "passive"))
      (node (ref "U2") (pin "5") (pinfunction "PROG_5") (pintype "input"))
    )
    (net (code "51") (name "Net-(U2-STAT)") (class "Default")
      (node (ref "LED3") (pin "C") (pinfunction "C_C") (pintype "passive"))
      (node (ref "U2") (pin "1") (pinfunction "STAT_1") (pintype "output"))
    )
    (net (code "52") (name "RESET") (class "Default")
      (node (ref "C1") (pin "2") (pinfunction "2_2") (pintype "passive"))
      (node (ref "IC1") (pin "29") (pinfunction "PC6(/RESET)_29") (pintype "bidirectional"))
      (node (ref "R5") (pin "1") (pinfunction "1_1") (pintype "passive"))
      (node (ref "S1") (pin "3") (pinfunction "3_3") (pintype "passive"))
      (node (ref "S1") (pin "4") (pinfunction "4_4") (pintype "passive"))
    )
    (net (code "53") (name "SCL") (class "Default")
      (node (ref "IC1") (pin "28") (pinfunction "PC5(ADC5/SCL)_28") (pintype "bidirectional"))
      (node (ref "JP6") (pin "1") (pinfunction "1_1") (pintype "passive"))
    )
    (net (code "54") (name "SDA") (class "Default")
      (node (ref "IC1") (pin "27") (pinfunction "PC4(ADC4/SDA)_27") (pintype "bidirectional"))
      (node (ref "JP6") (pin "2") (pinfunction "2_2") (pintype "passive"))
    )
    (net (code "55") (name "USB5V") (class "Default")
      (node (ref "C11") (pin "1") (pinfunction "1_1") (pintype "passive"))
      (node (ref "F1") (pin "1") (pinfunction "1_1") (pintype "bidirectional"))
      (node (ref "S2") (pin "1") (pinfunction "O_1") (pintype "passive"))
      (node (ref "U2") (pin "4") (pinfunction "VIN_4") (pintype "power_in"))
    )
    (net (code "56") (name "unconnected-(IC2-CTS-Pad23)") (class "Default")
      (node (ref "IC2") (pin "23") (pinfunction "CTS_23") (pintype "input"))
    )
    (net (code "57") (name "unconnected-(IC2-DCD-Pad1)") (class "Default")
      (node (ref "IC2") (pin "1") (pinfunction "DCD_1") (pintype "input"))
    )
    (net (code "58") (name "unconnected-(IC2-DSR-Pad27)") (class "Default")
      (node (ref "IC2") (pin "27") (pinfunction "DSR_27") (pintype "input"))
    )
    (net (code "59") (name "unconnected-(IC2-RI-Pad2)") (class "Default")
      (node (ref "IC2") (pin "2") (pinfunction "RI_2") (pintype "input"))
    )
    (net (code "60") (name "unconnected-(IC2-RTS-Pad24)") (class "Default")
      (node (ref "IC2") (pin "24") (pinfunction "RTS_24") (pintype "output"))
    )
    (net (code "61") (name "unconnected-(IC2-SUSPEND-Pad12)") (class "Default")
      (node (ref "IC2") (pin "12") (pinfunction "SUSPEND_12") (pintype "output"))
    )
    (net (code "62") (name "unconnected-(IC2-~{RST}-Pad9)") (class "Default")
      (node (ref "IC2") (pin "9") (pinfunction "~{RST}_9") (pintype "bidirectional"))
    )
    (net (code "63") (name "unconnected-(IC2-~{SUSPEND}-Pad11)") (class "Default")
      (node (ref "IC2") (pin "11") (pinfunction "~{SUSPEND}_11") (pintype "output"))
    )
    (net (code "64") (name "unconnected-(R6D-1-Pad4)") (class "Default")
      (node (ref "R6") (pin "4") (pinfunction "1_4") (pintype "passive"))
    )
    (net (code "65") (name "unconnected-(R6D-2-Pad5)") (class "Default")
      (node (ref "R6") (pin "5") (pinfunction "2_5") (pintype "passive"))
    )
    (net (code "66") (name "unconnected-(U1-PadID)") (class "Default")
      (node (ref "U1") (pin "ID") (pinfunction "ID_ID") (pintype "bidirectional"))
    )
  )
)
